# BW2098_MIPI_CAM.net
KiCad netlist of a schematic drawn in Altium Designer
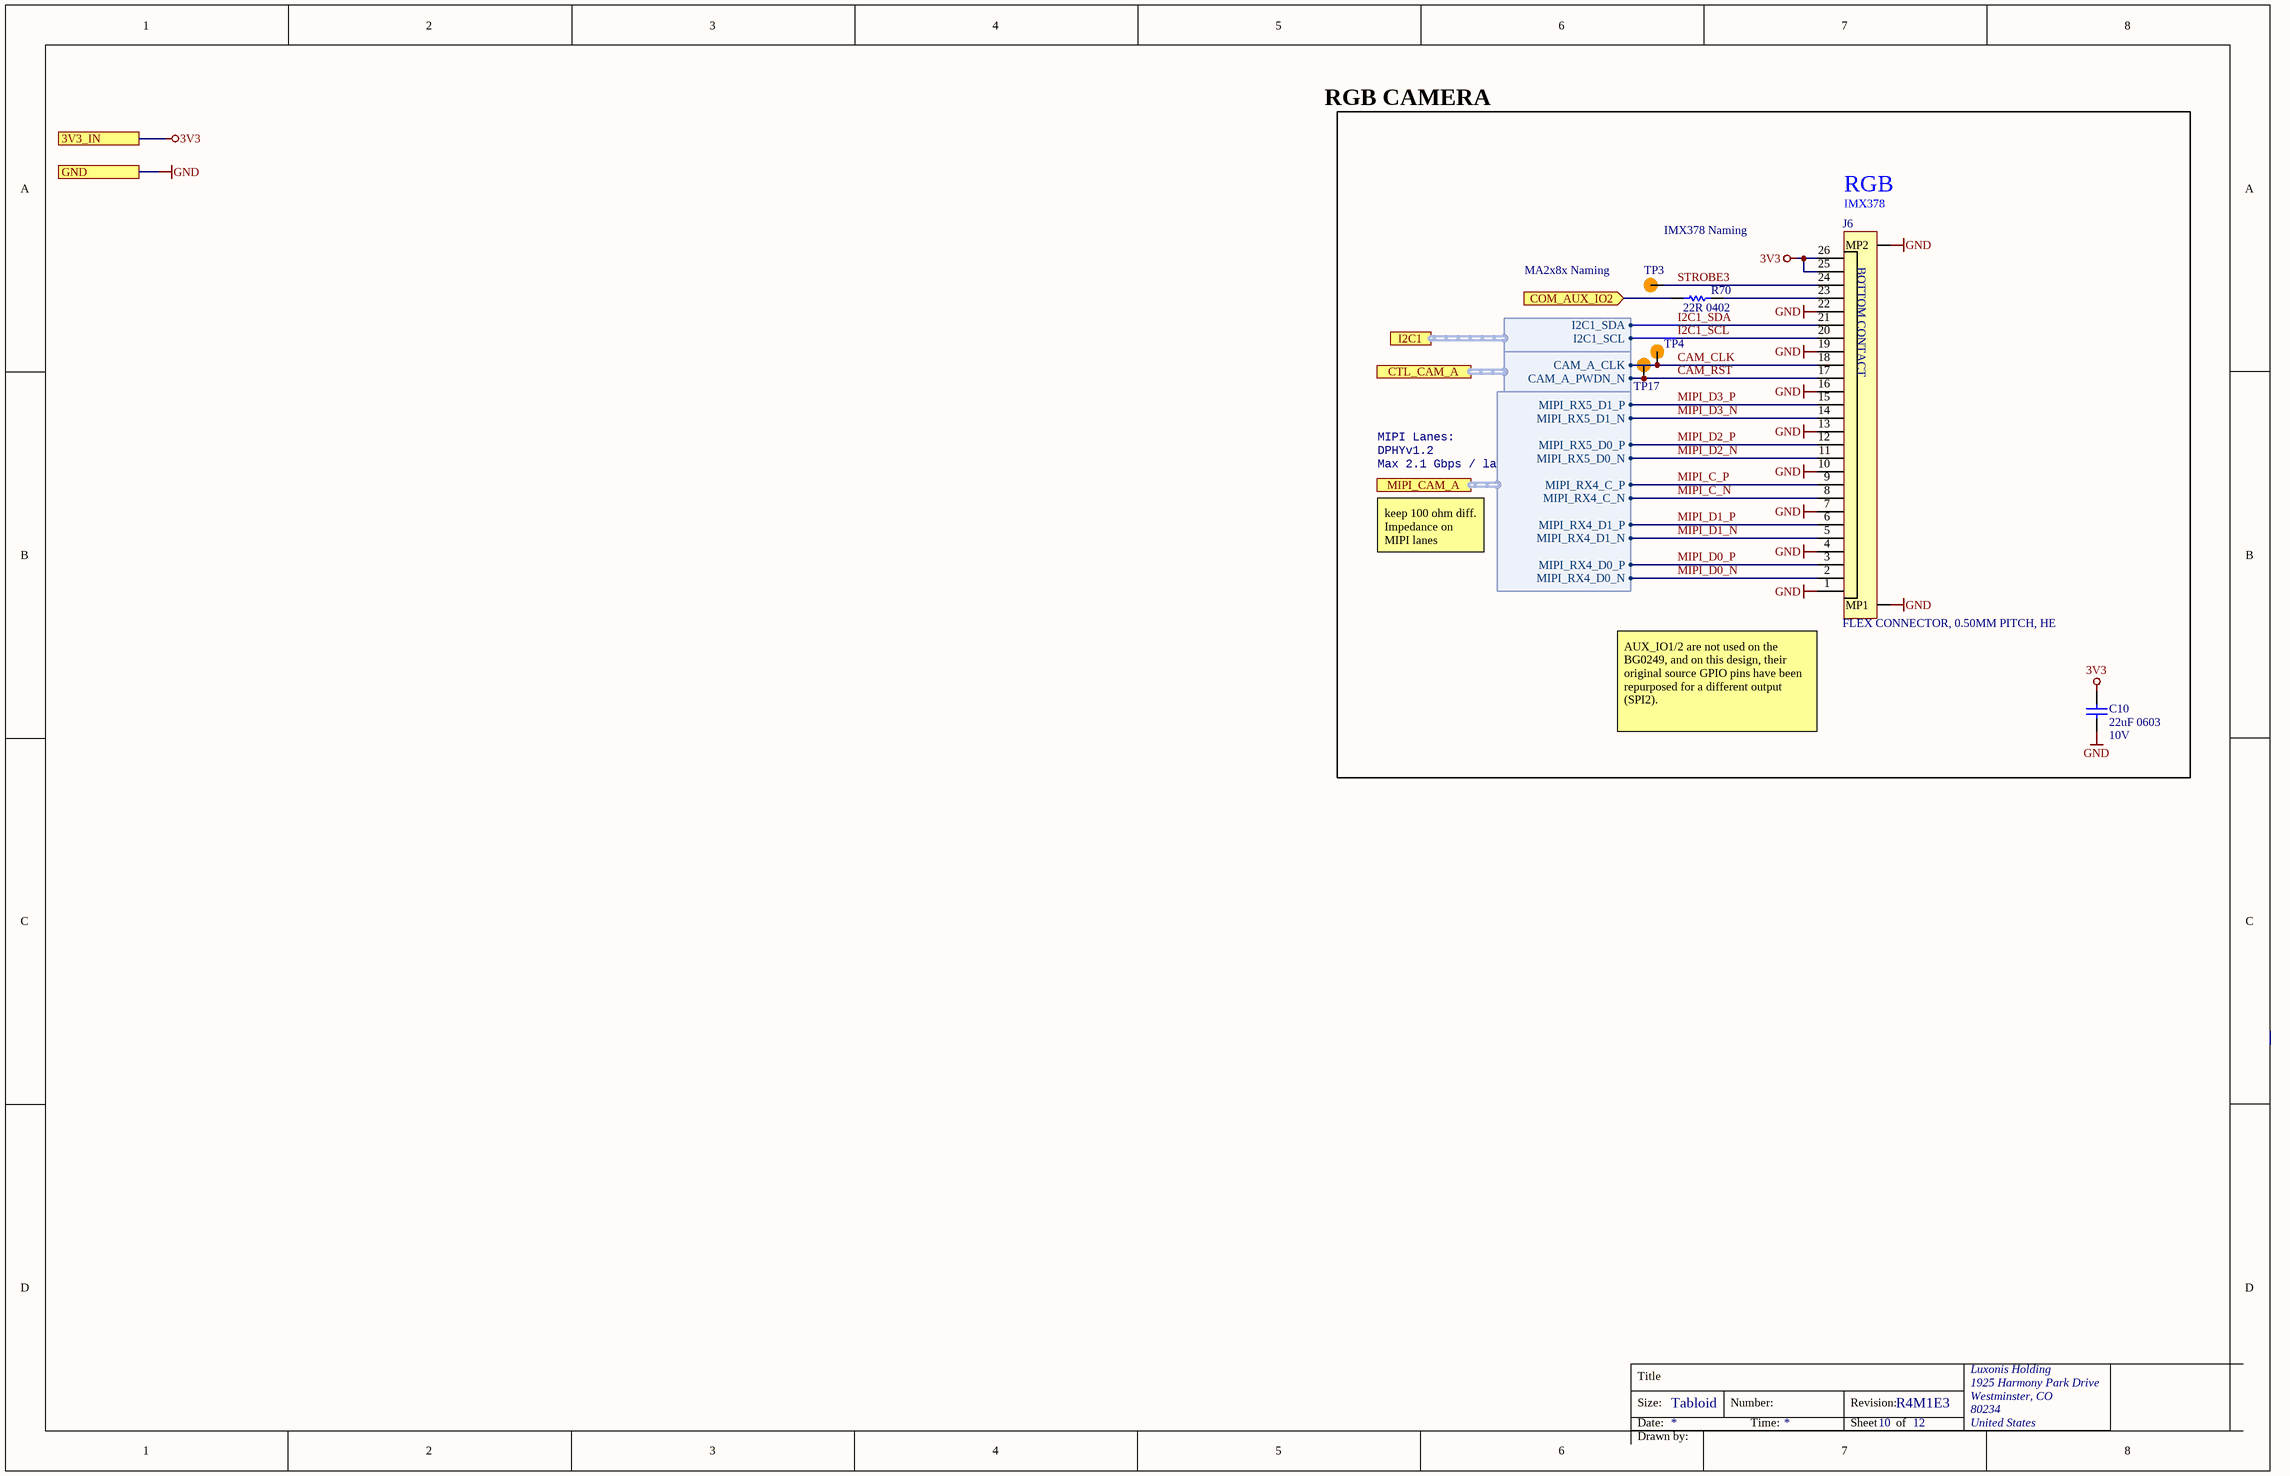
[diagram p0: BW2098_MIPI_CAM.SchDoc]

(export (version "E")
  (design (tool "Eeschema 10.0.6"))
  (components
    (comp (ref "C10")
      (value "22uF 0603")
      (footprint "CAP_Altium_Vault_Generic:CAPC0603(1608)100_N")
      (description "CAP CER 22UF 10V X5R 0603 20%")
      (fields (field (name "TOLERANCE") "20%") (field (name "VOLTAGE RATING") "10V"))
      (libsource (lib "LuxonisMaster") (part "GRM188R61A226ME15D"))
    )
    (comp (ref "J6")
      (value "FLEX CONNECTOR, 0.50MM PITCH, HE")
      (footprint "LuxonisMaster:F32R-1A7H1-11026")
      (description "26 Position FFC, FPC Connector Contacts, Bottom 0.020\" (0.50mm) Surface Mount, Right Angle")
      (libsource (lib "LuxonisMaster") (part "F32R-1A7H1-11026"))
    )
    (comp (ref "R70")
      (value "22R 0402")
      (footprint "RES_Altium_Vault_Generic:RESC0402(1005)_N")
      (description "RES SMD 22 OHM 1% 1/16W 0402")
      (fields (field (name "TOLERANCE") "1%"))
      (libsource (lib "LuxonisMaster") (part "RC0402FR-0722RL"))
    )
    (comp (ref "TP3")
      (value "TP100_200_NS")
      (footprint "LuxonisMaster:TP100_200_NS")
      (libsource (lib "LuxonisMaster") (part "TEST_POINT"))
    )
    (comp (ref "TP4")
      (value "TP100_200_NS")
      (footprint "LuxonisMaster:TP100_200_NS")
      (libsource (lib "LuxonisMaster") (part "TEST_POINT"))
    )
    (comp (ref "TP17")
      (value "TP100_200_NS")
      (footprint "LuxonisMaster:TP100_200_NS")
      (libsource (lib "LuxonisMaster") (part "TEST_POINT"))
    )
  )
  (nets
    (net (code "4") (name "/CAM_CLK") (class "Default")
      (node (ref "J6") (pin "18") (pinfunction "18_18") (pintype "passive"))
      (node (ref "TP4") (pin "1") (pintype "passive"))
    )
    (net (code "5") (name "/CAM_RST") (class "Default")
      (node (ref "J6") (pin "17") (pinfunction "17_17") (pintype "passive"))
      (node (ref "TP17") (pin "1") (pintype "passive"))
    )
    (net (code "6") (name "/COM_AUX_IO2") (class "Default")
      (node (ref "R70") (pin "1") (pinfunction "1_1") (pintype "passive"))
    )
    (net (code "8") (name "/I2C1_SCL") (class "Default")
      (node (ref "J6") (pin "20") (pinfunction "20_20") (pintype "passive"))
    )
    (net (code "9") (name "/I2C1_SDA") (class "Default")
      (node (ref "J6") (pin "21") (pinfunction "21_21") (pintype "passive"))
    )
    (net (code "11") (name "/MIPI_C_N") (class "Default")
      (node (ref "J6") (pin "8") (pinfunction "8_8") (pintype "passive"))
    )
    (net (code "12") (name "/MIPI_C_P") (class "Default")
      (node (ref "J6") (pin "9") (pinfunction "9_9") (pintype "passive"))
    )
    (net (code "13") (name "/MIPI_D0_N") (class "Default")
      (node (ref "J6") (pin "2") (pinfunction "2_2") (pintype "passive"))
    )
    (net (code "14") (name "/MIPI_D0_P") (class "Default")
      (node (ref "J6") (pin "3") (pinfunction "3_3") (pintype "passive"))
    )
    (net (code "15") (name "/MIPI_D1_N") (class "Default")
      (node (ref "J6") (pin "5") (pinfunction "5_5") (pintype "passive"))
    )
    (net (code "16") (name "/MIPI_D1_P") (class "Default")
      (node (ref "J6") (pin "6") (pinfunction "6_6") (pintype "passive"))
    )
    (net (code "17") (name "/MIPI_D2_N") (class "Default")
      (node (ref "J6") (pin "11") (pinfunction "11_11") (pintype "passive"))
    )
    (net (code "18") (name "/MIPI_D2_P") (class "Default")
      (node (ref "J6") (pin "12") (pinfunction "12_12") (pintype "passive"))
    )
    (net (code "19") (name "/MIPI_D3_N") (class "Default")
      (node (ref "J6") (pin "14") (pinfunction "14_14") (pintype "passive"))
    )
    (net (code "20") (name "/MIPI_D3_P") (class "Default")
      (node (ref "J6") (pin "15") (pinfunction "15_15") (pintype "passive"))
    )
    (net (code "21") (name "/STROBE3") (class "Default")
      (node (ref "J6") (pin "24") (pinfunction "24_24") (pintype "passive"))
      (node (ref "TP3") (pin "1") (pintype "passive"))
    )
    (net (code "23") (name "3V3") (class "Default")
      (node (ref "C10") (pin "2") (pinfunction "2_2") (pintype "passive"))
      (node (ref "J6") (pin "25") (pinfunction "25_25") (pintype "passive"))
      (node (ref "J6") (pin "26") (pinfunction "26_26") (pintype "passive"))
    )
    (net (code "24") (name "GND") (class "Default")
      (node (ref "C10") (pin "1") (pinfunction "1_1") (pintype "passive"))
      (node (ref "J6") (pin "1") (pinfunction "1_1") (pintype "passive"))
      (node (ref "J6") (pin "10") (pinfunction "10_10") (pintype "passive"))
      (node (ref "J6") (pin "13") (pinfunction "13_13") (pintype "passive"))
      (node (ref "J6") (pin "16") (pinfunction "16_16") (pintype "passive"))
      (node (ref "J6") (pin "19") (pinfunction "19_19") (pintype "passive"))
      (node (ref "J6") (pin "22") (pinfunction "22_22") (pintype "passive"))
      (node (ref "J6") (pin "4") (pinfunction "4_4") (pintype "passive"))
      (node (ref "J6") (pin "7") (pinfunction "7_7") (pintype "passive"))
      (node (ref "J6") (pin "MP1") (pinfunction "MP1_MP1") (pintype "passive"))
      (node (ref "J6") (pin "MP2") (pinfunction "MP2_MP2") (pintype "passive"))
    )
    (net (code "25") (name "Net-(J6-Pad23)") (class "Default")
      (node (ref "J6") (pin "23") (pinfunction "23_23") (pintype "passive"))
      (node (ref "R70") (pin "2") (pinfunction "2_2") (pintype "passive"))
    )
  )
)
